# V1_2-.net
KiCad netlist of a schematic drawn in Altium Designer
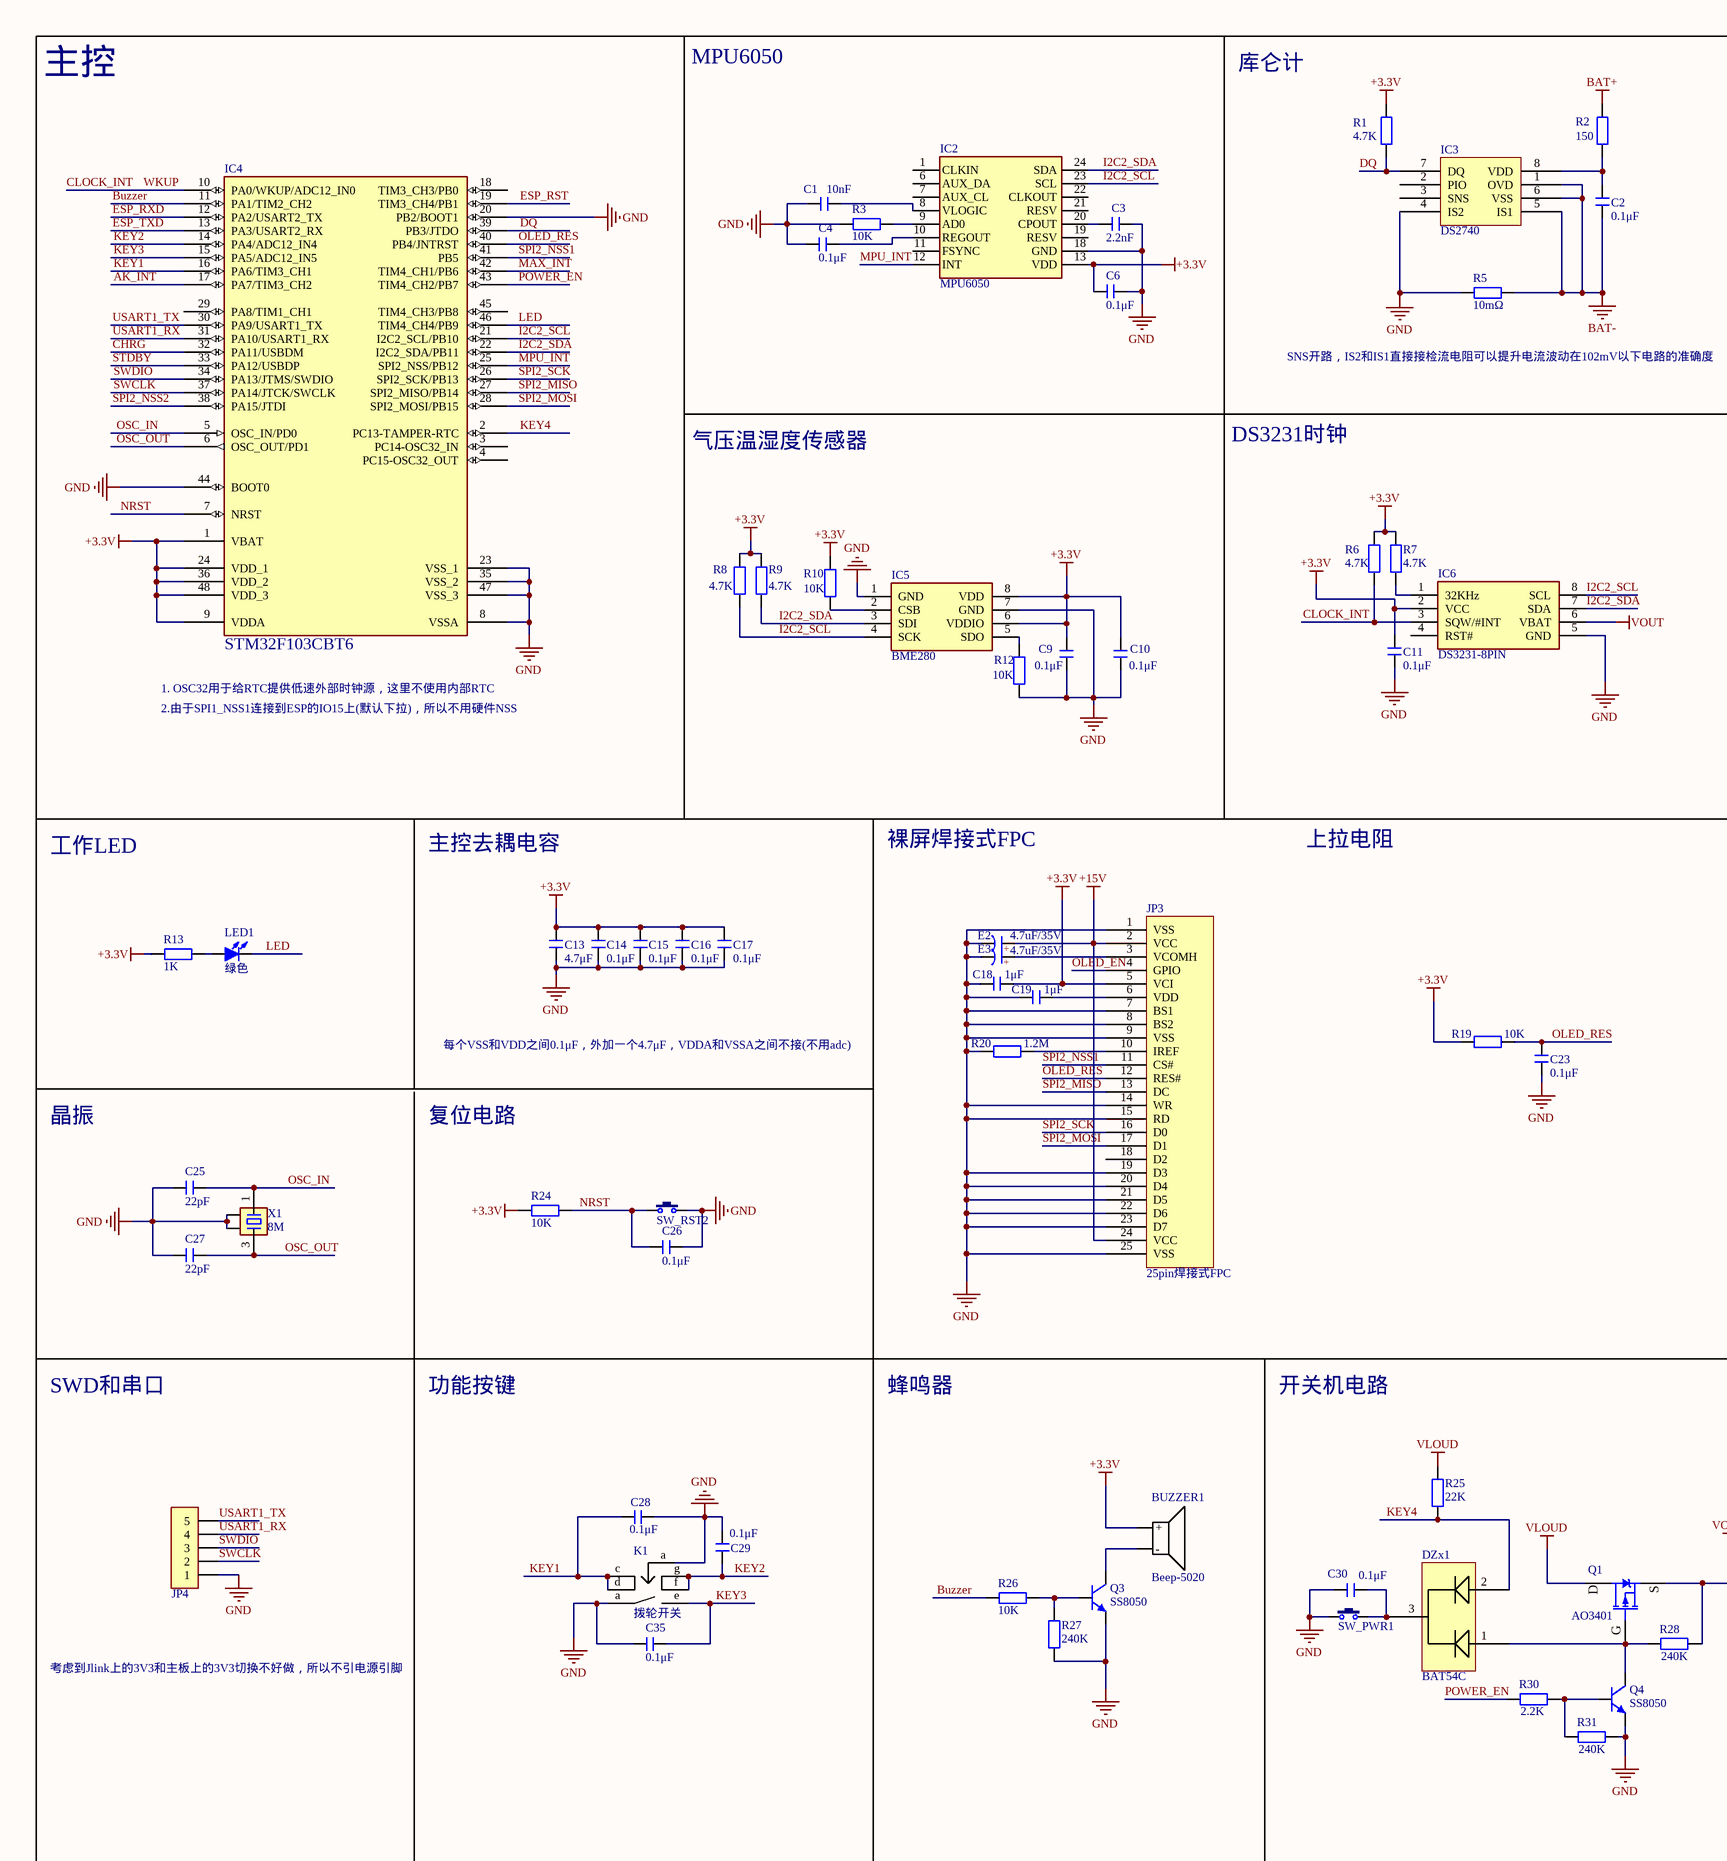
[diagram p0: V1.2-核心板.SchDoc, left]
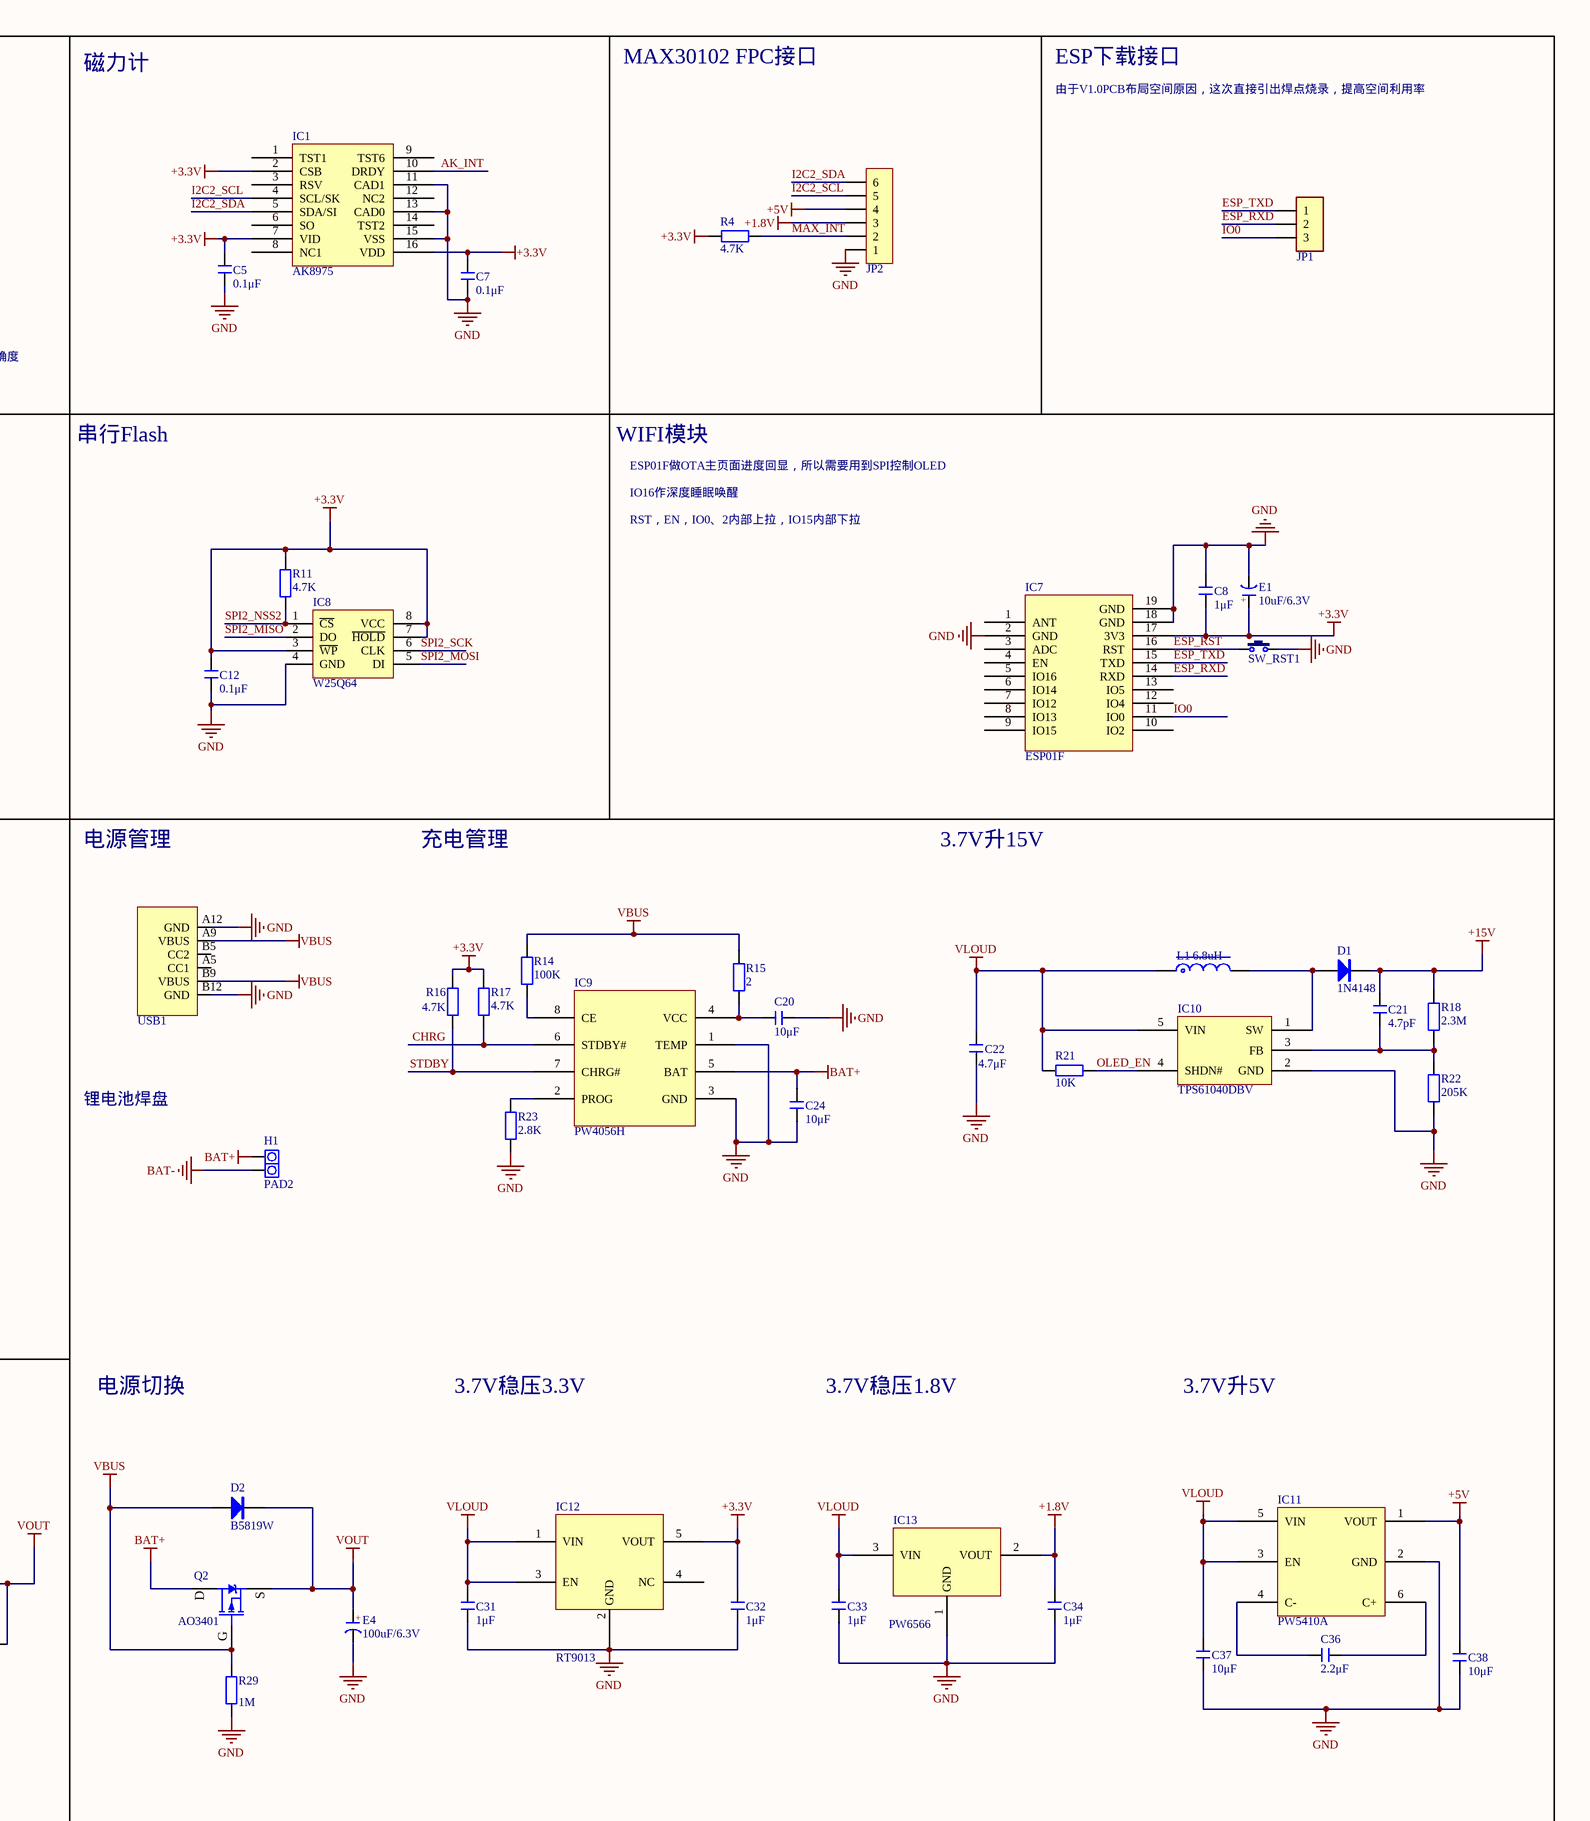
[diagram p1: V1.2-核心板.SchDoc, right]

(export (version "E")
  (design (tool "Eeschema 10.0.6"))
  (components
    (comp (ref "BUZZER1")
      (value "Beep-5020")
      (footprint "5020BUZZER")
      (description "贴片蜂鸣器5020最小封装")
      (libsource (lib "STM32_Watch") (part "Beep-5020"))
    )
    (comp (ref "C1")
      (value "10nF")
      (footprint "C 0603_L")
      (description "无极性贴片电容")
      (fields (field (name "版权归属") "源创客"))
      (libsource (lib "STM32_Watch") (part "C"))
    )
    (comp (ref "C2")
      (value "0.1μF")
      (footprint "C 0603_L")
      (description "无极性贴片电容")
      (fields (field (name "版权归属") "源创客"))
      (libsource (lib "STM32_Watch") (part "C"))
    )
    (comp (ref "C3")
      (value "2.2nF")
      (footprint "C 0603_L")
      (description "无极性贴片电容")
      (fields (field (name "版权归属") "源创客"))
      (libsource (lib "STM32_Watch") (part "C"))
    )
    (comp (ref "C4")
      (value "0.1μF")
      (footprint "C 0603_L")
      (description "无极性贴片电容")
      (fields (field (name "版权归属") "源创客"))
      (libsource (lib "STM32_Watch") (part "C"))
    )
    (comp (ref "C5")
      (value "0.1μF")
      (footprint "C 0603_L")
      (description "无极性贴片电容")
      (fields (field (name "版权归属") "源创客"))
      (libsource (lib "STM32_Watch") (part "C"))
    )
    (comp (ref "C6")
      (value "0.1μF")
      (footprint "C 0603_L")
      (description "无极性贴片电容")
      (fields (field (name "版权归属") "源创客"))
      (libsource (lib "STM32_Watch") (part "C"))
    )
    (comp (ref "C7")
      (value "0.1μF")
      (footprint "C 0603_L")
      (description "无极性贴片电容")
      (fields (field (name "版权归属") "源创客"))
      (libsource (lib "STM32_Watch") (part "C"))
    )
    (comp (ref "C8")
      (value "1μF")
      (footprint "C 0603_L")
      (description "无极性贴片电容")
      (fields (field (name "版权归属") "源创客"))
      (libsource (lib "STM32_Watch") (part "C"))
    )
    (comp (ref "C9")
      (value "0.1μF")
      (footprint "C 0603_L")
      (description "无极性贴片电容")
      (fields (field (name "版权归属") "源创客"))
      (libsource (lib "STM32_Watch") (part "C"))
    )
    (comp (ref "C10")
      (value "0.1μF")
      (footprint "C 0603_L")
      (description "无极性贴片电容")
      (fields (field (name "版权归属") "源创客"))
      (libsource (lib "STM32_Watch") (part "C"))
    )
    (comp (ref "C11")
      (value "0.1μF")
      (footprint "C 0603_L")
      (description "无极性贴片电容")
      (fields (field (name "版权归属") "源创客"))
      (libsource (lib "STM32_Watch") (part "C"))
    )
    (comp (ref "C12")
      (value "0.1μF")
      (footprint "C 0603_L")
      (description "无极性贴片电容")
      (fields (field (name "版权归属") "源创客"))
      (libsource (lib "STM32_Watch") (part "C"))
    )
    (comp (ref "C13")
      (value "4.7μF")
      (footprint "C 0603_L")
      (description "无极性贴片电容")
      (fields (field (name "版权归属") "源创客"))
      (libsource (lib "STM32_Watch") (part "C"))
    )
    (comp (ref "C14")
      (value "0.1μF")
      (footprint "C 0603_L")
      (description "无极性贴片电容")
      (fields (field (name "版权归属") "源创客"))
      (libsource (lib "STM32_Watch") (part "C"))
    )
    (comp (ref "C15")
      (value "0.1μF")
      (footprint "C 0603_L")
      (description "无极性贴片电容")
      (fields (field (name "版权归属") "源创客"))
      (libsource (lib "STM32_Watch") (part "C"))
    )
    (comp (ref "C16")
      (value "0.1μF")
      (footprint "C 0603_L")
      (description "无极性贴片电容")
      (fields (field (name "版权归属") "源创客"))
      (libsource (lib "STM32_Watch") (part "C"))
    )
    (comp (ref "C17")
      (value "0.1μF")
      (footprint "C 0603_L")
      (description "无极性贴片电容")
      (fields (field (name "版权归属") "源创客"))
      (libsource (lib "STM32_Watch") (part "C"))
    )
    (comp (ref "C18")
      (value "1μF")
      (footprint "C 0603_L")
      (description "无极性贴片电容")
      (fields (field (name "版权归属") "源创客"))
      (libsource (lib "STM32_Watch") (part "C"))
    )
    (comp (ref "C19")
      (value "1μF")
      (footprint "C 0603_L")
      (description "无极性贴片电容")
      (fields (field (name "版权归属") "源创客"))
      (libsource (lib "STM32_Watch") (part "C"))
    )
    (comp (ref "C20")
      (value "10μF")
      (footprint "C 0603_L")
      (description "无极性贴片电容")
      (fields (field (name "版权归属") "源创客"))
      (libsource (lib "STM32_Watch") (part "C"))
    )
    (comp (ref "C21")
      (value "4.7pF")
      (footprint "C 0603_L")
      (description "无极性贴片电容")
      (fields (field (name "版权归属") "源创客"))
      (libsource (lib "STM32_Watch") (part "C"))
    )
    (comp (ref "C22")
      (value "4.7μF")
      (footprint "C 0603_L")
      (description "无极性贴片电容")
      (fields (field (name "版权归属") "源创客"))
      (libsource (lib "STM32_Watch") (part "C"))
    )
    (comp (ref "C23")
      (value "0.1μF")
      (footprint "C 0603_L")
      (description "无极性贴片电容")
      (fields (field (name "版权归属") "源创客"))
      (libsource (lib "STM32_Watch") (part "C"))
    )
    (comp (ref "C24")
      (value "10μF")
      (footprint "C 0603_L")
      (description "无极性贴片电容")
      (fields (field (name "版权归属") "源创客"))
      (libsource (lib "STM32_Watch") (part "C"))
    )
    (comp (ref "C25")
      (value "22pF")
      (footprint "C 0603_L")
      (description "无极性贴片电容")
      (fields (field (name "版权归属") "源创客"))
      (libsource (lib "STM32_Watch") (part "C"))
    )
    (comp (ref "C26")
      (value "0.1μF")
      (footprint "C 0603_L")
      (description "无极性贴片电容")
      (fields (field (name "版权归属") "源创客"))
      (libsource (lib "STM32_Watch") (part "C"))
    )
    (comp (ref "C27")
      (value "22pF")
      (footprint "C 0603_L")
      (description "无极性贴片电容")
      (fields (field (name "版权归属") "源创客"))
      (libsource (lib "STM32_Watch") (part "C"))
    )
    (comp (ref "C28")
      (value "0.1μF")
      (footprint "C 0603_L")
      (description "无极性贴片电容")
      (fields (field (name "版权归属") "源创客"))
      (libsource (lib "STM32_Watch") (part "C"))
    )
    (comp (ref "C29")
      (value "0.1μF")
      (footprint "C 0603_L")
      (description "无极性贴片电容")
      (fields (field (name "版权归属") "源创客"))
      (libsource (lib "STM32_Watch") (part "C"))
    )
    (comp (ref "C30")
      (value "0.1μF")
      (footprint "C 0603_L")
      (description "无极性贴片电容")
      (fields (field (name "版权归属") "源创客"))
      (libsource (lib "STM32_Watch") (part "C"))
    )
    (comp (ref "C31")
      (value "1μF")
      (footprint "C 0603_L")
      (description "无极性贴片电容")
      (fields (field (name "版权归属") "源创客"))
      (libsource (lib "STM32_Watch") (part "C"))
    )
    (comp (ref "C32")
      (value "1μF")
      (footprint "C 0603_L")
      (description "无极性贴片电容")
      (fields (field (name "版权归属") "源创客"))
      (libsource (lib "STM32_Watch") (part "C"))
    )
    (comp (ref "C33")
      (value "1μF")
      (footprint "C 0603_L")
      (description "无极性贴片电容")
      (fields (field (name "版权归属") "源创客"))
      (libsource (lib "STM32_Watch") (part "C"))
    )
    (comp (ref "C34")
      (value "1μF")
      (footprint "C 0603_L")
      (description "无极性贴片电容")
      (fields (field (name "版权归属") "源创客"))
      (libsource (lib "STM32_Watch") (part "C"))
    )
    (comp (ref "C35")
      (value "0.1μF")
      (footprint "C 0603_L")
      (description "无极性贴片电容")
      (fields (field (name "版权归属") "源创客"))
      (libsource (lib "STM32_Watch") (part "C"))
    )
    (comp (ref "C36")
      (value "2.2μF")
      (footprint "C 0603_L")
      (description "无极性贴片电容")
      (fields (field (name "版权归属") "源创客"))
      (libsource (lib "STM32_Watch") (part "C"))
    )
    (comp (ref "C37")
      (value "10μF")
      (footprint "C 0603_L")
      (description "无极性贴片电容")
      (fields (field (name "版权归属") "源创客"))
      (libsource (lib "STM32_Watch") (part "C"))
    )
    (comp (ref "C38")
      (value "10μF")
      (footprint "C 0603_L")
      (description "无极性贴片电容")
      (fields (field (name "版权归属") "源创客"))
      (libsource (lib "STM32_Watch") (part "C"))
    )
    (comp (ref "D1")
      (value "1N4148")
      (footprint "SOD-123")
      (description "高速开关二极管")
      (fields (field (name "版权归属") "源创客"))
      (libsource (lib "STM32_Watch") (part "1N4148"))
    )
    (comp (ref "D2")
      (value "B5819W")
      (footprint "SOD-123")
      (description "肖特基二极管")
      (fields (field (name "版权归属") "源创客"))
      (libsource (lib "STM32_Watch") (part "B5819W"))
    )
    (comp (ref "DZx1")
      (value "BAT54C")
      (footprint "SOT23-3N")
      (description "双肖特基，共阴极")
      (libsource (lib "STM32_Watch") (part "BAT54C"))
    )
    (comp (ref "E1")
      (value "10uF/6.3V")
      (footprint "CD A(3216)")
      (description "贴片钽电容")
      (fields (field (name "版权归属") "源创客"))
      (libsource (lib "") (part "C-CD_1"))
    )
    (comp (ref "E2")
      (value "4.7uF/35V")
      (footprint "CD A(3216)")
      (description "贴片钽电容")
      (fields (field (name "版权归属") "源创客"))
      (libsource (lib "3.1   - 电阻-电容-电感") (part "C-CD"))
    )
    (comp (ref "E3")
      (value "4.7uF/35V")
      (footprint "CD A(3216)")
      (description "贴片钽电容")
      (fields (field (name "版权归属") "源创客"))
      (libsource (lib "3.1   - 电阻-电容-电感") (part "C-CD"))
    )
    (comp (ref "E4")
      (value "100uF/6.3V")
      (footprint "CD A(3216)")
      (description "贴片钽电容")
      (fields (field (name "版权归属") "源创客"))
      (libsource (lib "") (part "C-CD_1"))
    )
    (comp (ref "H1")
      (value "PAD2")
      (footprint "CHARGE_PAD")
      (description "引线焊盘")
      (fields (field (name "版权归属") "源创客"))
      (libsource (lib "STM32_Watch") (part "PAD2"))
    )
    (comp (ref "IC1")
      (value "AK8975")
      (footprint "QFN16 4x4_M")
      (description "采用高灵敏度霍尔传感器技术的三轴电子罗盘IC。\r\n最适合步行城市导航，用于手机和其他便携式设备")
      (libsource (lib "STM32_Watch") (part "AK8975"))
    )
    (comp (ref "IC2")
      (value "MPU6050")
      (footprint "QFN24 4x4_M")
      (description "陀螺仪")
      (libsource (lib "STM32_Watch") (part "MPU6050"))
    )
    (comp (ref "IC3")
      (value "DS2740")
      (footprint "MSOP8_L")
      (description "高精度库仑计")
      (libsource (lib "STM32_Watch") (part "DS2740"))
    )
    (comp (ref "IC4")
      (value "STM32F103CBT6")
      (footprint "LQFP48 7X7_M")
      (description "Flash:128/RAM:20/IO:48")
      (fields (field (name "版权归属") "源创客"))
      (libsource (lib "STM32_Watch") (part "STM32F103CB"))
    )
    (comp (ref "IC5")
      (value "BME280")
      (footprint "BME280")
      (description "气压，湿度，温度传感器")
      (libsource (lib "STM32_Watch") (part "BME280"))
    )
    (comp (ref "IC6")
      (value "DS3231-8PIN")
      (footprint "SOP8_N")
      (libsource (lib "STM32_Watch") (part "DS3231-8PIN"))
    )
    (comp (ref "IC7") (value "ESP01F") (footprint "ESP-01F") (libsource (lib "STM32_Watch") (part "ESP01F")))
    (comp (ref "IC8")
      (value "W25Q64")
      (footprint "SOP8W_N")
      (description "外置Flash")
      (fields (field (name "版权归属") "源创客"))
      (libsource (lib "1.1   - IC芯片") (part "W25Qxx"))
    )
    (comp (ref "IC9")
      (value "PW4056H")
      (footprint "SOP-8_L4.9-W3.9-P1.27-LS6.0-BL-EP3.1")
      (description "PW4056H 是一款完整的采用恒定电流/恒定电压的高压、大电流、单节鲤离子电池线性充电IC，最高耐压可达 28V，6.5V 自动过压保护，充电电流可达 1A。")
      (libsource (lib "STM32_Watch") (part "PW4056H"))
    )
    (comp (ref "IC10")
      (value "TPS61040DBV")
      (footprint "SOT23-5L")
      (description "28V、400mA 开关升压转换器，适用于 LCD 和白光 LED")
      (libsource (lib "STM32_Watch") (part "TPS61040DBV"))
    )
    (comp (ref "IC11")
      (value "PW5410A")
      (footprint "SOT23-6")
      (description "低噪声，恒频 1.2MHZ，输入电压范围2.7v-5v，5v固定输出电压，输出电流250mA的DCDC升压")
      (libsource (lib "STM32_Watch") (part "PW5410A"))
    )
    (comp (ref "IC12")
      (value "RT9013")
      (footprint "SOT23-5L")
      (libsource (lib "STM32_Watch") (part "RT9013"))
    )
    (comp (ref "IC13")
      (value "PW6566")
      (footprint "SOT23-3L")
      (description "PW6566 系列是使用 CMOS 技术开发的低压差，高精度 输出电压，低消耗电流正电压型电压稳压器")
      (libsource (lib "STM32_Watch") (part "PW6566"))
    )
    (comp (ref "JP1")
      (value "HDR-1X3")
      (footprint "TEST_POINT_3")
      (description "3P接插件")
      (fields (field (name "版权归属") "源创客"))
      (libsource (lib "STM32_Watch") (part "Header 3"))
    )
    (comp (ref "JP2")
      (value "FPC1.0-6P")
      (footprint "FPC0.5 2H-WS-6P")
      (description "FPC连接器")
      (fields (field (name "版权归属") "源创客"))
      (libsource (lib "STM32_Watch") (part "FPC-6P"))
    )
    (comp (ref "JP3")
      (value "25pin焊接式FPC")
      (footprint "25pin焊接式FPC")
      (libsource (lib "STM32_Watch") (part "25pin焊接式FPC"))
    )
    (comp (ref "JP4")
      (value "HDR-1X5")
      (footprint "TEST_POINT_5")
      (description "5P接插件")
      (fields (field (name "版权归属") "源创客"))
      (libsource (lib "STM32_Watch") (part "Header 5"))
    )
    (comp (ref "K1") (value "拨轮开关") (footprint "拨轮开关") (libsource (lib "STM32_Watch") (part "拨轮开关")))
    (comp (ref "L1")
      (value "6.8uH")
      (footprint "NR3015")
      (description "NR磁胶电感")
      (fields (field (name "版权归属") "源创客"))
      (libsource (lib "STM32_Watch") (part "L-NR"))
    )
    (comp (ref "LED1")
      (value "绿色")
      (footprint "LED 0603G")
      (description "贴片LED")
      (fields (field (name "版权归属") "源创客"))
      (libsource (lib "STM32_Watch") (part "LED-SMD"))
    )
    (comp (ref "Q1")
      (value "AO3401")
      (footprint "SOT23-3N")
      (description "P沟道场效应管")
      (fields (field (name "版权归属") "源创客"))
      (libsource (lib "STM32_Watch") (part "AO3401"))
    )
    (comp (ref "Q2")
      (value "AO3401")
      (footprint "SOT23-3N")
      (description "P沟道场效应管")
      (fields (field (name "版权归属") "源创客"))
      (libsource (lib "STM32_Watch") (part "AO3401"))
    )
    (comp (ref "Q3")
      (value "SS8050")
      (footprint "SOT23-3N")
      (description "高频放大-NPN型")
      (fields (field (name "版权归属") "源创客"))
      (libsource (lib "STM32_Watch") (part "8050-SMD"))
    )
    (comp (ref "Q4")
      (value "SS8050")
      (footprint "SOT23-3N")
      (description "高频放大-NPN型")
      (fields (field (name "版权归属") "源创客"))
      (libsource (lib "STM32_Watch") (part "8050-SMD"))
    )
    (comp (ref "R1")
      (value "4.7K")
      (footprint "R 0603_L")
      (description "贴片电阻")
      (fields (field (name "版权归属") "源创客"))
      (libsource (lib "STM32_Watch") (part "R"))
    )
    (comp (ref "R2")
      (value "150")
      (footprint "R 0603_L")
      (description "贴片电阻")
      (fields (field (name "版权归属") "源创客"))
      (libsource (lib "STM32_Watch") (part "R"))
    )
    (comp (ref "R3")
      (value "10K")
      (footprint "R 0603_L")
      (description "贴片电阻")
      (fields (field (name "版权归属") "源创客"))
      (libsource (lib "STM32_Watch") (part "R"))
    )
    (comp (ref "R4")
      (value "4.7K")
      (footprint "R 0603_L")
      (description "贴片电阻")
      (fields (field (name "版权归属") "源创客"))
      (libsource (lib "STM32_Watch") (part "R"))
    )
    (comp (ref "R5")
      (value "10mΩ")
      (footprint "R 0603_L")
      (description "贴片电阻")
      (fields (field (name "版权归属") "源创客"))
      (libsource (lib "STM32_Watch") (part "R"))
    )
    (comp (ref "R6")
      (value "4.7K")
      (footprint "R 0603_L")
      (description "贴片电阻")
      (fields (field (name "版权归属") "源创客"))
      (libsource (lib "STM32_Watch") (part "R"))
    )
    (comp (ref "R7")
      (value "4.7K")
      (footprint "R 0603_L")
      (description "贴片电阻")
      (fields (field (name "版权归属") "源创客"))
      (libsource (lib "STM32_Watch") (part "R"))
    )
    (comp (ref "R8")
      (value "4.7K")
      (footprint "R 0603_L")
      (description "贴片电阻")
      (fields (field (name "版权归属") "源创客"))
      (libsource (lib "STM32_Watch") (part "R"))
    )
    (comp (ref "R9")
      (value "4.7K")
      (footprint "R 0603_L")
      (description "贴片电阻")
      (fields (field (name "版权归属") "源创客"))
      (libsource (lib "STM32_Watch") (part "R"))
    )
    (comp (ref "R10")
      (value "10K")
      (footprint "R 0603_L")
      (description "贴片电阻")
      (fields (field (name "版权归属") "源创客"))
      (libsource (lib "STM32_Watch") (part "R"))
    )
    (comp (ref "R11")
      (value "4.7K")
      (footprint "R 0603_L")
      (description "贴片电阻")
      (fields (field (name "版权归属") "源创客"))
      (libsource (lib "STM32_Watch") (part "R"))
    )
    (comp (ref "R12")
      (value "10K")
      (footprint "R 0603_L")
      (description "贴片电阻")
      (fields (field (name "版权归属") "源创客"))
      (libsource (lib "STM32_Watch") (part "R"))
    )
    (comp (ref "R13")
      (value "1K")
      (footprint "R 0603_L")
      (description "贴片电阻")
      (fields (field (name "版权归属") "源创客"))
      (libsource (lib "STM32_Watch") (part "R"))
    )
    (comp (ref "R14")
      (value "100K")
      (footprint "R 0603_L")
      (description "贴片电阻")
      (fields (field (name "版权归属") "源创客"))
      (libsource (lib "STM32_Watch") (part "R"))
    )
    (comp (ref "R15")
      (value "2")
      (footprint "R 0603_L")
      (description "贴片电阻")
      (fields (field (name "版权归属") "源创客"))
      (libsource (lib "STM32_Watch") (part "R"))
    )
    (comp (ref "R16")
      (value "4.7K")
      (footprint "R 0603_L")
      (description "贴片电阻")
      (fields (field (name "版权归属") "源创客"))
      (libsource (lib "STM32_Watch") (part "R"))
    )
    (comp (ref "R17")
      (value "4.7K")
      (footprint "R 0603_L")
      (description "贴片电阻")
      (fields (field (name "版权归属") "源创客"))
      (libsource (lib "STM32_Watch") (part "R"))
    )
    (comp (ref "R18")
      (value "2.3M")
      (footprint "R 0603_L")
      (description "贴片电阻")
      (fields (field (name "版权归属") "源创客"))
      (libsource (lib "STM32_Watch") (part "R"))
    )
    (comp (ref "R19")
      (value "10K")
      (footprint "R 0603_L")
      (description "贴片电阻")
      (fields (field (name "版权归属") "源创客"))
      (libsource (lib "STM32_Watch") (part "R"))
    )
    (comp (ref "R20")
      (value "1.2M")
      (footprint "R 0603_L")
      (description "贴片电阻")
      (fields (field (name "版权归属") "源创客"))
      (libsource (lib "STM32_Watch") (part "R"))
    )
    (comp (ref "R21")
      (value "10K")
      (footprint "R 0603_L")
      (description "贴片电阻")
      (fields (field (name "版权归属") "源创客"))
      (libsource (lib "STM32_Watch") (part "R"))
    )
    (comp (ref "R22")
      (value "205K")
      (footprint "R 0603_L")
      (description "贴片电阻")
      (fields (field (name "版权归属") "源创客"))
      (libsource (lib "STM32_Watch") (part "R"))
    )
    (comp (ref "R23")
      (value "2.8K")
      (footprint "R 0603_L")
      (description "贴片电阻")
      (fields (field (name "版权归属") "源创客"))
      (libsource (lib "STM32_Watch") (part "R"))
    )
    (comp (ref "R24")
      (value "10K")
      (footprint "R 0603_L")
      (description "贴片电阻")
      (fields (field (name "版权归属") "源创客"))
      (libsource (lib "STM32_Watch") (part "R"))
    )
    (comp (ref "R25")
      (value "22K")
      (footprint "R 0603_L")
      (description "贴片电阻")
      (fields (field (name "版权归属") "源创客"))
      (libsource (lib "STM32_Watch") (part "R"))
    )
    (comp (ref "R26")
      (value "10K")
      (footprint "R 0603_L")
      (description "贴片电阻")
      (fields (field (name "版权归属") "源创客"))
      (libsource (lib "STM32_Watch") (part "R"))
    )
    (comp (ref "R27")
      (value "240K")
      (footprint "R 0603_L")
      (description "贴片电阻")
      (fields (field (name "版权归属") "源创客"))
      (libsource (lib "STM32_Watch") (part "R"))
    )
    (comp (ref "R28")
      (value "240K")
      (footprint "R 0603_L")
      (description "贴片电阻")
      (fields (field (name "版权归属") "源创客"))
      (libsource (lib "STM32_Watch") (part "R"))
    )
    (comp (ref "R29")
      (value "1M")
      (footprint "R 0603_L")
      (description "贴片电阻")
      (fields (field (name "版权归属") "源创客"))
      (libsource (lib "STM32_Watch") (part "R"))
    )
    (comp (ref "R30")
      (value "2.2K")
      (footprint "R 0603_L")
      (description "贴片电阻")
      (fields (field (name "版权归属") "源创客"))
      (libsource (lib "STM32_Watch") (part "R"))
    )
    (comp (ref "R31")
      (value "240K")
      (footprint "R 0603_L")
      (description "贴片电阻")
      (fields (field (name "版权归属") "源创客"))
      (libsource (lib "STM32_Watch") (part "R"))
    )
    (comp (ref "SW_PWR1")
      (value "3")
      (footprint "KEY-SMD_UK-B0264-SP25Y")
      (description "2x4x3.5轻触开关")
      (fields (field (name "版权归属") "源创客"))
      (libsource (lib "STM32_Watch") (part "TSW 2x4x3.5"))
    )
    (comp (ref "SW_RST1")
      (value "3x4x2")
      (footprint "SW-SMD_L4.0-W3.0-LS4.6")
      (description "3x4x2开关")
      (fields (field (name "版权归属") "源创客"))
      (libsource (lib "STM32_Watch") (part "TSW 3x4x2"))
    )
    (comp (ref "SW_RST2")
      (value "3x4x2")
      (footprint "SW-SMD_L4.0-W3.0-LS4.6")
      (description "3x4x2开关")
      (fields (field (name "版权归属") "源创客"))
      (libsource (lib "STM32_Watch") (part "TSW 3x4x2"))
    )
    (comp (ref "USB1")
      (value "918-418K2023S40006")
      (footprint "USB-C-SMD_918-418K2023S40006")
      (description "连接器类型:Type-C;标准:USB 3.1;公母:母座;触点数量:6;端口数量:1;安装方式:卧贴;额定电流 - 电源:-;工作温度范围:-40℃~+85℃;")
      (fields (field (name "MANUFACTURER") "精拓金"))
      (libsource (lib "STM32_Watch") (part "TYPE-C 6PIN"))
    )
    (comp (ref "X1")
      (value "8M")
      (footprint "OSC 3225-4P")
      (description "4脚无源晶振")
      (fields (field (name "版权归属") "源创客"))
      (libsource (lib "STM32_Watch") (part "XTAL-4P"))
    )
  )
  (nets
    (net (code "1") (name "+1.8V") (class "Default")
      (node (ref "C34") (pin "1") (pinfunction "1_1") (pintype "passive"))
      (node (ref "IC13") (pin "2") (pinfunction "VOUT_2") (pintype "passive"))
      (node (ref "JP2") (pin "3") (pinfunction "3_3") (pintype "passive"))
    )
    (net (code "2") (name "+3.3V") (class "Default")
      (node (ref "BUZZER1") (pin "1") (pinfunction "+_1") (pintype "passive"))
      (node (ref "C10") (pin "1") (pinfunction "1_1") (pintype "passive"))
      (node (ref "C11") (pin "1") (pinfunction "1_1") (pintype "passive"))
      (node (ref "C12") (pin "2") (pinfunction "2_2") (pintype "passive"))
      (node (ref "C13") (pin "2") (pinfunction "2_2") (pintype "passive"))
      (node (ref "C14") (pin "2") (pinfunction "2_2") (pintype "passive"))
      (node (ref "C15") (pin "2") (pinfunction "2_2") (pintype "passive"))
      (node (ref "C16") (pin "2") (pinfunction "2_2") (pintype "passive"))
      (node (ref "C17") (pin "2") (pinfunction "2_2") (pintype "passive"))
      (node (ref "C18") (pin "2") (pinfunction "2_2") (pintype "passive"))
      (node (ref "C32") (pin "1") (pinfunction "1_1") (pintype "passive"))
      (node (ref "C5") (pin "2") (pinfunction "2_2") (pintype "passive"))
      (node (ref "C6") (pin "2") (pinfunction "2_2") (pintype "passive"))
      (node (ref "C7") (pin "2") (pinfunction "2_2") (pintype "passive"))
      (node (ref "C8") (pin "1") (pinfunction "1_1") (pintype "passive"))
      (node (ref "C9") (pin "1") (pinfunction "1_1") (pintype "passive"))
      (node (ref "E1") (pin "1") (pinfunction "A_1") (pintype "passive"))
      (node (ref "IC1") (pin "16") (pinfunction "VDD_16") (pintype "passive"))
      (node (ref "IC1") (pin "2") (pinfunction "CSB_2") (pintype "passive"))
      (node (ref "IC1") (pin "7") (pinfunction "VID_7") (pintype "passive"))
      (node (ref "IC12") (pin "5") (pinfunction "VOUT_5") (pintype "passive"))
      (node (ref "IC2") (pin "13") (pinfunction "VDD_13") (pintype "passive"))
      (node (ref "IC4") (pin "1") (pinfunction "VBAT_1") (pintype "power_in"))
      (node (ref "IC4") (pin "24") (pinfunction "VDD_1_24") (pintype "power_in"))
      (node (ref "IC4") (pin "36") (pinfunction "VDD_2_36") (pintype "power_in"))
      (node (ref "IC4") (pin "48") (pinfunction "VDD_3_48") (pintype "power_in"))
      (node (ref "IC4") (pin "9") (pinfunction "VDDA_9") (pintype "power_in"))
      (node (ref "IC5") (pin "6") (pinfunction "VDDIO_6") (pintype "passive"))
      (node (ref "IC5") (pin "8") (pinfunction "VDD_8") (pintype "passive"))
      (node (ref "IC6") (pin "2") (pinfunction "VCC_2") (pintype "passive"))
      (node (ref "IC7") (pin "17") (pinfunction "3V3_17") (pintype "passive"))
      (node (ref "IC8") (pin "3") (pinfunction "~{WP}_3") (pintype "passive"))
      (node (ref "IC8") (pin "7") (pinfunction "~{HOLD}_7") (pintype "passive"))
      (node (ref "IC8") (pin "8") (pinfunction "VCC_8") (pintype "passive"))
      (node (ref "JP3") (pin "5") (pinfunction "VCI_5") (pintype "passive"))
      (node (ref "R1") (pin "2") (pinfunction "2_2") (pintype "passive"))
      (node (ref "R10") (pin "2") (pinfunction "2_2") (pintype "passive"))
      (node (ref "R11") (pin "2") (pinfunction "2_2") (pintype "passive"))
      (node (ref "R13") (pin "2") (pinfunction "2_2") (pintype "passive"))
      (node (ref "R16") (pin "2") (pinfunction "2_2") (pintype "passive"))
      (node (ref "R17") (pin "2") (pinfunction "2_2") (pintype "passive"))
      (node (ref "R19") (pin "1") (pinfunction "1_1") (pintype "passive"))
      (node (ref "R24") (pin "2") (pinfunction "2_2") (pintype "passive"))
      (node (ref "R4") (pin "2") (pinfunction "2_2") (pintype "passive"))
      (node (ref "R6") (pin "1") (pinfunction "1_1") (pintype "passive"))
      (node (ref "R7") (pin "1") (pinfunction "1_1") (pintype "passive"))
      (node (ref "R8") (pin "1") (pinfunction "1_1") (pintype "passive"))
      (node (ref "R9") (pin "1") (pinfunction "1_1") (pintype "passive"))
    )
    (net (code "3") (name "+5V") (class "Default")
      (node (ref "C38") (pin "1") (pinfunction "1_1") (pintype "passive"))
      (node (ref "IC11") (pin "1") (pinfunction "VOUT_1") (pintype "passive"))
      (node (ref "JP2") (pin "4") (pinfunction "4_4") (pintype "passive"))
    )
    (net (code "4") (name "+15V") (class "Default")
      (node (ref "C21") (pin "2") (pinfunction "2_2") (pintype "passive"))
      (node (ref "D1") (pin "2") (pinfunction "K_2") (pintype "passive"))
      (node (ref "E2") (pin "1") (pinfunction "A_1") (pintype "passive"))
      (node (ref "JP3") (pin "2") (pinfunction "VCC_2") (pintype "passive"))
      (node (ref "JP3") (pin "24") (pinfunction "VCC_24") (pintype "passive"))
      (node (ref "R18") (pin "2") (pinfunction "2_2") (pintype "passive"))
    )
    (net (code "5") (name "/AK_INT") (class "Default")
      (node (ref "IC1") (pin "10") (pinfunction "DRDY_10") (pintype "passive"))
      (node (ref "IC4") (pin "17") (pinfunction "PA7/TIM3_CH2_17") (pintype "bidirectional"))
    )
    (net (code "6") (name "/Buzzer") (class "Default")
      (node (ref "IC4") (pin "11") (pinfunction "PA1/TIM2_CH2_11") (pintype "bidirectional"))
      (node (ref "R26") (pin "1") (pinfunction "1_1") (pintype "passive"))
    )
    (net (code "7") (name "/CHRG") (class "Default")
      (node (ref "IC4") (pin "32") (pinfunction "PA11/USBDM_32") (pintype "bidirectional"))
      (node (ref "IC9") (pin "6") (pinfunction "STDBY#_6") (pintype "passive"))
      (node (ref "R17") (pin "1") (pinfunction "1_1") (pintype "passive"))
    )
    (net (code "8") (name "/CLOCK_INT") (class "Default")
      (node (ref "IC4") (pin "10") (pinfunction "PA0/WKUP/ADC12_IN0_10") (pintype "bidirectional"))
      (node (ref "IC6") (pin "3") (pinfunction "SQW/#INT_3") (pintype "passive"))
      (node (ref "R6") (pin "2") (pinfunction "2_2") (pintype "passive"))
    )
    (net (code "9") (name "/DQ") (class "Default")
      (node (ref "IC3") (pin "7") (pinfunction "DQ_7") (pintype "passive"))
      (node (ref "IC4") (pin "39") (pinfunction "PB3/JTDO_39") (pintype "bidirectional"))
      (node (ref "R1") (pin "1") (pinfunction "1_1") (pintype "passive"))
    )
    (net (code "10") (name "/ESP_RST") (class "Default")
      (node (ref "IC4") (pin "19") (pinfunction "TIM3_CH4/PB1_19") (pintype "bidirectional"))
      (node (ref "IC7") (pin "16") (pinfunction "RST_16") (pintype "passive"))
      (node (ref "SW_RST1") (pin "1") (pinfunction "1_1") (pintype "passive"))
    )
    (net (code "11") (name "/ESP_RXD") (class "Default")
      (node (ref "IC4") (pin "12") (pinfunction "PA2/USART2_TX_12") (pintype "bidirectional"))
      (node (ref "IC7") (pin "14") (pinfunction "RXD_14") (pintype "passive"))
      (node (ref "JP1") (pin "2") (pinfunction "2_2") (pintype "passive"))
    )
    (net (code "12") (name "/ESP_TXD") (class "Default")
      (node (ref "IC4") (pin "13") (pinfunction "PA3/USART2_RX_13") (pintype "bidirectional"))
      (node (ref "IC7") (pin "15") (pinfunction "TXD_15") (pintype "passive"))
      (node (ref "JP1") (pin "1") (pinfunction "1_1") (pintype "passive"))
    )
    (net (code "13") (name "/I2C2_SCL") (class "Default")
      (node (ref "IC1") (pin "4") (pinfunction "SCL/SK_4") (pintype "passive"))
      (node (ref "IC2") (pin "23") (pinfunction "SCL_23") (pintype "passive"))
      (node (ref "IC4") (pin "21") (pinfunction "I2C2_SCL/PB10_21") (pintype "bidirectional"))
      (node (ref "IC5") (pin "4") (pinfunction "SCK_4") (pintype "passive"))
      (node (ref "IC6") (pin "8") (pinfunction "SCL_8") (pintype "passive"))
      (node (ref "JP2") (pin "5") (pinfunction "5_5") (pintype "passive"))
      (node (ref "R8") (pin "2") (pinfunction "2_2") (pintype "passive"))
    )
    (net (code "14") (name "/I2C2_SDA") (class "Default")
      (node (ref "IC1") (pin "5") (pinfunction "SDA/SI_5") (pintype "passive"))
      (node (ref "IC2") (pin "24") (pinfunction "SDA_24") (pintype "passive"))
      (node (ref "IC4") (pin "22") (pinfunction "I2C2_SDA/PB11_22") (pintype "bidirectional"))
      (node (ref "IC5") (pin "3") (pinfunction "SDI_3") (pintype "passive"))
      (node (ref "IC6") (pin "7") (pinfunction "SDA_7") (pintype "passive"))
      (node (ref "JP2") (pin "6") (pinfunction "6_6") (pintype "passive"))
      (node (ref "R9") (pin "2") (pinfunction "2_2") (pintype "passive"))
    )
    (net (code "15") (name "/IO0") (class "Default")
      (node (ref "IC7") (pin "11") (pinfunction "IO0_11") (pintype "passive"))
      (node (ref "JP1") (pin "3") (pinfunction "3_3") (pintype "passive"))
    )
    (net (code "16") (name "/KEY1") (class "Default")
      (node (ref "C28") (pin "1") (pinfunction "1_1") (pintype "passive"))
      (node (ref "IC4") (pin "16") (pinfunction "PA6/TIM3_CH1_16") (pintype "bidirectional"))
      (node (ref "K1") (pin "c") (pinfunction "c_c") (pintype "passive"))
      (node (ref "K1") (pin "d") (pinfunction "d_d") (pintype "passive"))
    )
    (net (code "17") (name "/KEY2") (class "Default")
      (node (ref "C29") (pin "1") (pinfunction "1_1") (pintype "passive"))
      (node (ref "IC4") (pin "14") (pinfunction "PA4/ADC12_IN4_14") (pintype "bidirectional"))
      (node (ref "K1") (pin "f") (pinfunction "f_f") (pintype "passive"))
      (node (ref "K1") (pin "g") (pinfunction "g_g") (pintype "passive"))
    )
    (net (code "18") (name "/KEY3") (class "Default")
      (node (ref "C35") (pin "1") (pinfunction "1_1") (pintype "passive"))
      (node (ref "IC4") (pin "15") (pinfunction "PA5/ADC12_IN5_15") (pintype "bidirectional"))
      (node (ref "K1") (pin "e") (pinfunction "e_e") (pintype "passive"))
    )
    (net (code "19") (name "/KEY4") (class "Default")
      (node (ref "DZx1") (pin "2") (pinfunction "2_2") (pintype "passive"))
      (node (ref "IC4") (pin "2") (pinfunction "PC13-TAMPER-RTC_2") (pintype "bidirectional"))
      (node (ref "R25") (pin "2") (pinfunction "2_2") (pintype "passive"))
    )
    (net (code "20") (name "/LED") (class "Default")
      (node (ref "IC4") (pin "46") (pinfunction "TIM4_CH4/PB9_46") (pintype "bidirectional"))
      (node (ref "LED1") (pin "2") (pinfunction "K_2") (pintype "passive"))
    )
    (net (code "21") (name "/MAX_INT") (class "Default")
      (node (ref "IC4") (pin "42") (pinfunction "TIM4_CH1/PB6_42") (pintype "bidirectional"))
      (node (ref "JP2") (pin "2") (pinfunction "2_2") (pintype "passive"))
      (node (ref "R4") (pin "1") (pinfunction "1_1") (pintype "passive"))
    )
    (net (code "22") (name "/MPU_INT") (class "Default")
      (node (ref "IC2") (pin "12") (pinfunction "INT_12") (pintype "passive"))
      (node (ref "IC4") (pin "25") (pinfunction "SPI2_NSS/PB12_25") (pintype "bidirectional"))
    )
    (net (code "23") (name "/NRST") (class "Default")
      (node (ref "C26") (pin "2") (pinfunction "2_2") (pintype "passive"))
      (node (ref "IC4") (pin "7") (pinfunction "NRST_7") (pintype "bidirectional"))
      (node (ref "R24") (pin "1") (pinfunction "1_1") (pintype "passive"))
      (node (ref "SW_RST2") (pin "1") (pinfunction "1_1") (pintype "passive"))
    )
    (net (code "24") (name "/OLED_EN") (class "Default")
      (node (ref "IC10") (pin "4") (pinfunction "SHDN#_4") (pintype "passive"))
      (node (ref "JP3") (pin "4") (pinfunction "GPIO_4") (pintype "passive"))
      (node (ref "R21") (pin "1") (pinfunction "1_1") (pintype "passive"))
    )
    (net (code "25") (name "/OLED_RES") (class "Default")
      (node (ref "C23") (pin "2") (pinfunction "2_2") (pintype "passive"))
      (node (ref "IC4") (pin "40") (pinfunction "PB4/JNTRST_40") (pintype "bidirectional"))
      (node (ref "JP3") (pin "12") (pinfunction "RES#_12") (pintype "passive"))
      (node (ref "R19") (pin "2") (pinfunction "2_2") (pintype "passive"))
    )
    (net (code "26") (name "/OSC_IN") (class "Default")
      (node (ref "C25") (pin "1") (pinfunction "1_1") (pintype "passive"))
      (node (ref "IC4") (pin "5") (pinfunction "OSC_IN/PD0_5") (pintype "input"))
      (node (ref "X1") (pin "1") (pinfunction "1_1") (pintype "passive"))
    )
    (net (code "27") (name "/OSC_OUT") (class "Default")
      (node (ref "C27") (pin "1") (pinfunction "1_1") (pintype "passive"))
      (node (ref "IC4") (pin "6") (pinfunction "OSC_OUT/PD1_6") (pintype "output"))
      (node (ref "X1") (pin "3") (pinfunction "3_3") (pintype "passive"))
    )
    (net (code "28") (name "/POWER_EN") (class "Default")
      (node (ref "IC4") (pin "43") (pinfunction "TIM4_CH2/PB7_43") (pintype "bidirectional"))
      (node (ref "R30") (pin "2") (pinfunction "2_2") (pintype "passive"))
    )
    (net (code "29") (name "/SPI2_MISO") (class "Default")
      (node (ref "IC4") (pin "27") (pinfunction "SPI2_MISO/PB14_27") (pintype "bidirectional"))
      (node (ref "IC8") (pin "2") (pinfunction "DO_2") (pintype "passive"))
      (node (ref "JP3") (pin "13") (pinfunction "DC_13") (pintype "passive"))
    )
    (net (code "30") (name "/SPI2_MOSI") (class "Default")
      (node (ref "IC4") (pin "28") (pinfunction "SPI2_MOSI/PB15_28") (pintype "bidirectional"))
      (node (ref "IC8") (pin "5") (pinfunction "DI_5") (pintype "passive"))
      (node (ref "JP3") (pin "17") (pinfunction "D1_17") (pintype "passive"))
    )
    (net (code "31") (name "/SPI2_NSS1") (class "Default")
      (node (ref "IC4") (pin "41") (pinfunction "PB5_41") (pintype "bidirectional"))
      (node (ref "JP3") (pin "11") (pinfunction "CS#_11") (pintype "passive"))
    )
    (net (code "32") (name "/SPI2_NSS2") (class "Default")
      (node (ref "IC4") (pin "38") (pinfunction "PA15/JTDI_38") (pintype "bidirectional"))
      (node (ref "IC8") (pin "1") (pinfunction "~{CS}_1") (pintype "passive"))
      (node (ref "R11") (pin "1") (pinfunction "1_1") (pintype "passive"))
    )
    (net (code "33") (name "/SPI2_SCK") (class "Default")
      (node (ref "IC4") (pin "26") (pinfunction "SPI2_SCK/PB13_26") (pintype "bidirectional"))
      (node (ref "IC8") (pin "6") (pinfunction "CLK_6") (pintype "passive"))
      (node (ref "JP3") (pin "16") (pinfunction "D0_16") (pintype "passive"))
    )
    (net (code "34") (name "/STDBY") (class "Default")
      (node (ref "IC4") (pin "33") (pinfunction "PA12/USBDP_33") (pintype "bidirectional"))
      (node (ref "IC9") (pin "7") (pinfunction "CHRG#_7") (pintype "passive"))
      (node (ref "R16") (pin "1") (pinfunction "1_1") (pintype "passive"))
    )
    (net (code "35") (name "/SWCLK") (class "Default")
      (node (ref "IC4") (pin "37") (pinfunction "PA14/JTCK/SWCLK_37") (pintype "bidirectional"))
      (node (ref "JP4") (pin "2") (pinfunction "2_2") (pintype "passive"))
    )
    (net (code "36") (name "/SWDIO") (class "Default")
      (node (ref "IC4") (pin "34") (pinfunction "PA13/JTMS/SWDIO_34") (pintype "bidirectional"))
      (node (ref "JP4") (pin "3") (pinfunction "3_3") (pintype "passive"))
    )
    (net (code "37") (name "/USART1_RX") (class "Default")
      (node (ref "IC4") (pin "31") (pinfunction "PA10/USART1_RX_31") (pintype "bidirectional"))
      (node (ref "JP4") (pin "4") (pinfunction "4_4") (pintype "passive"))
    )
    (net (code "38") (name "/USART1_TX") (class "Default")
      (node (ref "IC4") (pin "30") (pinfunction "PA9/USART1_TX_30") (pintype "bidirectional"))
      (node (ref "JP4") (pin "5") (pinfunction "5_5") (pintype "passive"))
    )
    (net (code "39") (name "BAT+") (class "Default")
      (node (ref "C24") (pin "1") (pinfunction "1_1") (pintype "passive"))
      (node (ref "H1") (pin "+") (pinfunction "+_+") (pintype "passive"))
      (node (ref "IC9") (pin "5") (pinfunction "BAT_5") (pintype "passive"))
      (node (ref "Q2") (pin "3") (pinfunction "D_3") (pintype "passive"))
      (node (ref "R2") (pin "2") (pinfunction "2_2") (pintype "passive"))
    )
    (net (code "40") (name "BAT-") (class "Default")
      (node (ref "C2") (pin "1") (pinfunction "1_1") (pintype "passive"))
      (node (ref "H1") (pin "-") (pinfunction "-_-") (pintype "passive"))
      (node (ref "IC3") (pin "1") (pinfunction "OVD_1") (pintype "passive"))
      (node (ref "IC3") (pin "5") (pinfunction "IS1_5") (pintype "passive"))
      (node (ref "IC3") (pin "6") (pinfunction "VSS_6") (pintype "passive"))
      (node (ref "R5") (pin "1") (pinfunction "1_1") (pintype "passive"))
    )
    (net (code "41") (name "GND") (class "Default")
      (node (ref "C1") (pin "2") (pinfunction "2_2") (pintype "passive"))
      (node (ref "C10") (pin "2") (pinfunction "2_2") (pintype "passive"))
      (node (ref "C11") (pin "2") (pinfunction "2_2") (pintype "passive"))
      (node (ref "C12") (pin "1") (pinfunction "1_1") (pintype "passive"))
      (node (ref "C13") (pin "1") (pinfunction "1_1") (pintype "passive"))
      (node (ref "C14") (pin "1") (pinfunction "1_1") (pintype "passive"))
      (node (ref "C15") (pin "1") (pinfunction "1_1") (pintype "passive"))
      (node (ref "C16") (pin "1") (pinfunction "1_1") (pintype "passive"))
      (node (ref "C17") (pin "1") (pinfunction "1_1") (pintype "passive"))
      (node (ref "C18") (pin "1") (pinfunction "1_1") (pintype "passive"))
      (node (ref "C19") (pin "1") (pinfunction "1_1") (pintype "passive"))
      (node (ref "C20") (pin "1") (pinfunction "1_1") (pintype "passive"))
      (node (ref "C22") (pin "1") (pinfunction "1_1") (pintype "passive"))
      (node (ref "C23") (pin "1") (pinfunction "1_1") (pintype "passive"))
      (node (ref "C24") (pin "2") (pinfunction "2_2") (pintype "passive"))
      (node (ref "C25") (pin "2") (pinfunction "2_2") (pintype "passive"))
      (node (ref "C26") (pin "1") (pinfunction "1_1") (pintype "passive"))
      (node (ref "C27") (pin "2") (pinfunction "2_2") (pintype "passive"))
      (node (ref "C28") (pin "2") (pinfunction "2_2") (pintype "passive"))
      (node (ref "C29") (pin "2") (pinfunction "2_2") (pintype "passive"))
      (node (ref "C3") (pin "1") (pinfunction "1_1") (pintype "passive"))
      (node (ref "C30") (pin "1") (pinfunction "1_1") (pintype "passive"))
      (node (ref "C31") (pin "2") (pinfunction "2_2") (pintype "passive"))
      (node (ref "C32") (pin "2") (pinfunction "2_2") (pintype "passive"))
      (node (ref "C33") (pin "2") (pinfunction "2_2") (pintype "passive"))
      (node (ref "C34") (pin "2") (pinfunction "2_2") (pintype "passive"))
      (node (ref "C35") (pin "2") (pinfunction "2_2") (pintype "passive"))
      (node (ref "C37") (pin "1") (pinfunction "1_1") (pintype "passive"))
      (node (ref "C38") (pin "2") (pinfunction "2_2") (pintype "passive"))
      (node (ref "C4") (pin "2") (pinfunction "2_2") (pintype "passive"))
      (node (ref "C5") (pin "1") (pinfunction "1_1") (pintype "passive"))
      (node (ref "C6") (pin "1") (pinfunction "1_1") (pintype "passive"))
      (node (ref "C7") (pin "1") (pinfunction "1_1") (pintype "passive"))
      (node (ref "C8") (pin "2") (pinfunction "2_2") (pintype "passive"))
      (node (ref "C9") (pin "2") (pinfunction "2_2") (pintype "passive"))
      (node (ref "E1") (pin "2") (pinfunction "K_2") (pintype "passive"))
      (node (ref "E2") (pin "2") (pinfunction "K_2") (pintype "passive"))
      (node (ref "E3") (pin "2") (pinfunction "K_2") (pintype "passive"))
      (node (ref "E4") (pin "2") (pinfunction "K_2") (pintype "passive"))
      (node (ref "IC1") (pin "11") (pinfunction "CAD1_11") (pintype "passive"))
      (node (ref "IC1") (pin "13") (pinfunction "CAD0_13") (pintype "passive"))
      (node (ref "IC1") (pin "15") (pinfunction "VSS_15") (pintype "passive"))
      (node (ref "IC10") (pin "2") (pinfunction "GND_2") (pintype "passive"))
      (node (ref "IC11") (pin "2") (pinfunction "GND_2") (pintype "passive"))
      (node (ref "IC12") (pin "2") (pinfunction "GND_2") (pintype "passive"))
      (node (ref "IC13") (pin "1") (pinfunction "GND_1") (pintype "passive"))
      (node (ref "IC2") (pin "18") (pinfunction "GND_18") (pintype "passive"))
      (node (ref "IC3") (pin "4") (pinfunction "IS2_4") (pintype "passive"))
      (node (ref "IC4") (pin "20") (pinfunction "PB2/BOOT1_20") (pintype "bidirectional"))
      (node (ref "IC4") (pin "23") (pinfunction "VSS_1_23") (pintype "power_in"))
      (node (ref "IC4") (pin "35") (pinfunction "VSS_2_35") (pintype "power_in"))
      (node (ref "IC4") (pin "44") (pinfunction "BOOT0_44") (pintype "bidirectional"))
      (node (ref "IC4") (pin "47") (pinfunction "VSS_3_47") (pintype "power_in"))
      (node (ref "IC4") (pin "8") (pinfunction "VSSA_8") (pintype "power_in"))
      (node (ref "IC5") (pin "1") (pinfunction "GND_1") (pintype "passive"))
      (node (ref "IC5") (pin "7") (pinfunction "GND_7") (pintype "passive"))
      (node (ref "IC6") (pin "5") (pinfunction "GND_5") (pintype "passive"))
      (node (ref "IC7") (pin "18") (pinfunction "GND_18") (pintype "passive"))
      (node (ref "IC7") (pin "19") (pinfunction "GND_19") (pintype "passive"))
      (node (ref "IC7") (pin "2") (pinfunction "GND_2") (pintype "passive"))
      (node (ref "IC8") (pin "4") (pinfunction "GND_4") (pintype "passive"))
      (node (ref "IC9") (pin "1") (pinfunction "TEMP_1") (pintype "passive"))
      (node (ref "IC9") (pin "3") (pinfunction "GND_3") (pintype "passive"))
      (node (ref "JP2") (pin "1") (pinfunction "1_1") (pintype "passive"))
      (node (ref "JP3") (pin "1") (pinfunction "VSS_1") (pintype "passive"))
      (node (ref "JP3") (pin "14") (pinfunction "WR_14") (pintype "passive"))
      (node (ref "JP3") (pin "15") (pinfunction "RD_15") (pintype "passive"))
      (node (ref "JP3") (pin "19") (pinfunction "D3_19") (pintype "passive"))
      (node (ref "JP3") (pin "20") (pinfunction "D4_20") (pintype "passive"))
      (node (ref "JP3") (pin "21") (pinfunction "D5_21") (pintype "passive"))
      (node (ref "JP3") (pin "22") (pinfunction "D6_22") (pintype "passive"))
      (node (ref "JP3") (pin "23") (pinfunction "D7_23") (pintype "passive"))
      (node (ref "JP3") (pin "25") (pinfunction "VSS_25") (pintype "passive"))
      (node (ref "JP3") (pin "7") (pinfunction "BS1_7") (pintype "passive"))
      (node (ref "JP3") (pin "8") (pinfunction "BS2_8") (pintype "passive"))
      (node (ref "JP3") (pin "9") (pinfunction "VSS_9") (pintype "passive"))
      (node (ref "JP4") (pin "1") (pinfunction "1_1") (pintype "passive"))
      (node (ref "K1") (pin "a") (pinfunction "a_a") (pintype "passive"))
      (node (ref "Q3") (pin "2") (pinfunction "E_2") (pintype "passive"))
      (node (ref "Q4") (pin "2") (pinfunction "E_2") (pintype "passive"))
      (node (ref "R12") (pin "1") (pinfunction "1_1") (pintype "passive"))
      (node (ref "R20") (pin "1") (pinfunction "1_1") (pintype "passive"))
      (node (ref "R22") (pin "1") (pinfunction "1_1") (pintype "passive"))
      (node (ref "R23") (pin "1") (pinfunction "1_1") (pintype "passive"))
      (node (ref "R27") (pin "1") (pinfunction "1_1") (pintype "passive"))
      (node (ref "R29") (pin "2") (pinfunction "2_2") (pintype "passive"))
      (node (ref "R3") (pin "2") (pinfunction "2_2") (pintype "passive"))
      (node (ref "R31") (pin "1") (pinfunction "1_1") (pintype "passive"))
      (node (ref "R5") (pin "2") (pinfunction "2_2") (pintype "passive"))
      (node (ref "SW_PWR1") (pin "2") (pinfunction "2_2") (pintype "passive"))
      (node (ref "SW_RST1") (pin "2") (pinfunction "2_2") (pintype "passive"))
      (node (ref "SW_RST2") (pin "2") (pinfunction "2_2") (pintype "passive"))
      (node (ref "USB1") (pin "A12") (pinfunction "GND_A12") (pintype "passive"))
      (node (ref "USB1") (pin "B12") (pinfunction "GND_B12") (pintype "passive"))
      (node (ref "X1") (pin "2") (pinfunction "2_2") (pintype "passive"))
      (node (ref "X1") (pin "4") (pinfunction "4_4") (pintype "passive"))
    )
    (net (code "42") (name "Net-(BUZZER1--)") (class "Default")
      (node (ref "BUZZER1") (pin "2") (pinfunction "-_2") (pintype "passive"))
      (node (ref "Q3") (pin "3") (pinfunction "C_3") (pintype "passive"))
    )
    (net (code "43") (name "Net-(C30-Pad2)") (class "Default")
      (node (ref "C30") (pin "2") (pinfunction "2_2") (pintype "passive"))
      (node (ref "DZx1") (pin "3") (pinfunction "3_3") (pintype "passive"))
      (node (ref "SW_PWR1") (pin "1") (pinfunction "1_1") (pintype "passive"))
    )
    (net (code "44") (name "Net-(D1-A)") (class "Default")
      (node (ref "D1") (pin "1") (pinfunction "A_1") (pintype "passive"))
      (node (ref "IC10") (pin "1") (pinfunction "SW_1") (pintype "passive"))
      (node (ref "L1") (pin "2") (pinfunction "2_2") (pintype "passive"))
    )
    (net (code "45") (name "Net-(E3-A)") (class "Default")
      (node (ref "E3") (pin "1") (pinfunction "A_1") (pintype "passive"))
      (node (ref "JP3") (pin "3") (pinfunction "VCOMH_3") (pintype "passive"))
    )
    (net (code "46") (name "Net-(IC2-AD0)") (class "Default")
      (node (ref "IC2") (pin "9") (pinfunction "AD0_9") (pintype "passive"))
      (node (ref "R3") (pin "1") (pinfunction "1_1") (pintype "passive"))
    )
    (net (code "47") (name "Net-(IC2-CPOUT)") (class "Default")
      (node (ref "C3") (pin "2") (pinfunction "2_2") (pintype "passive"))
      (node (ref "IC2") (pin "20") (pinfunction "CPOUT_20") (pintype "passive"))
    )
    (net (code "48") (name "Net-(IC2-REGOUT)") (class "Default")
      (node (ref "C4") (pin "1") (pinfunction "1_1") (pintype "passive"))
      (node (ref "IC2") (pin "10") (pinfunction "REGOUT_10") (pintype "passive"))
    )
    (net (code "49") (name "Net-(IC2-VLOGIC)") (class "Default")
      (node (ref "C1") (pin "1") (pinfunction "1_1") (pintype "passive"))
      (node (ref "IC2") (pin "8") (pinfunction "VLOGIC_8") (pintype "passive"))
    )
    (net (code "50") (name "Net-(IC3-VDD)") (class "Default")
      (node (ref "C2") (pin "2") (pinfunction "2_2") (pintype "passive"))
      (node (ref "IC3") (pin "8") (pinfunction "VDD_8") (pintype "passive"))
      (node (ref "R2") (pin "1") (pinfunction "1_1") (pintype "passive"))
    )
    (net (code "51") (name "Net-(IC5-CSB)") (class "Default")
      (node (ref "IC5") (pin "2") (pinfunction "CSB_2") (pintype "passive"))
      (node (ref "R10") (pin "1") (pinfunction "1_1") (pintype "passive"))
    )
    (net (code "52") (name "Net-(IC5-SDO)") (class "Default")
      (node (ref "IC5") (pin "5") (pinfunction "SDO_5") (pintype "passive"))
      (node (ref "R12") (pin "2") (pinfunction "2_2") (pintype "passive"))
    )
    (net (code "53") (name "Net-(IC6-32KHz)") (class "Default")
      (node (ref "IC6") (pin "1") (pinfunction "32KHz_1") (pintype "passive"))
      (node (ref "R7") (pin "2") (pinfunction "2_2") (pintype "passive"))
    )
    (net (code "54") (name "Net-(IC9-CE)") (class "Default")
      (node (ref "IC9") (pin "8") (pinfunction "CE_8") (pintype "passive"))
      (node (ref "R14") (pin "1") (pinfunction "1_1") (pintype "passive"))
    )
    (net (code "55") (name "Net-(IC9-PROG)") (class "Default")
      (node (ref "IC9") (pin "2") (pinfunction "PROG_2") (pintype "passive"))
      (node (ref "R23") (pin "2") (pinfunction "2_2") (pintype "passive"))
    )
    (net (code "56") (name "Net-(IC9-VCC)") (class "Default")
      (node (ref "C20") (pin "2") (pinfunction "2_2") (pintype "passive"))
      (node (ref "IC9") (pin "4") (pinfunction "VCC_4") (pintype "passive"))
      (node (ref "R15") (pin "1") (pinfunction "1_1") (pintype "passive"))
    )
    (net (code "57") (name "Net-(IC10-FB)") (class "Default")
      (node (ref "C21") (pin "1") (pinfunction "1_1") (pintype "passive"))
      (node (ref "IC10") (pin "3") (pinfunction "FB_3") (pintype "passive"))
      (node (ref "R18") (pin "1") (pinfunction "1_1") (pintype "passive"))
      (node (ref "R22") (pin "2") (pinfunction "2_2") (pintype "passive"))
    )
    (net (code "58") (name "Net-(IC11-C+)") (class "Default")
      (node (ref "C36") (pin "1") (pinfunction "1_1") (pintype "passive"))
      (node (ref "IC11") (pin "6") (pinfunction "C+_6") (pintype "passive"))
    )
    (net (code "59") (name "Net-(IC11-C-)") (class "Default")
      (node (ref "C36") (pin "2") (pinfunction "2_2") (pintype "passive"))
      (node (ref "IC11") (pin "4") (pinfunction "C-_4") (pintype "passive"))
    )
    (net (code "60") (name "Net-(JP3-IREF)") (class "Default")
      (node (ref "JP3") (pin "10") (pinfunction "IREF_10") (pintype "passive"))
      (node (ref "R20") (pin "2") (pinfunction "2_2") (pintype "passive"))
    )
    (net (code "61") (name "Net-(JP3-VDD)") (class "Default")
      (node (ref "C19") (pin "2") (pinfunction "2_2") (pintype "passive"))
      (node (ref "JP3") (pin "6") (pinfunction "VDD_6") (pintype "passive"))
    )
    (net (code "62") (name "Net-(LED1-A)") (class "Default")
      (node (ref "LED1") (pin "1") (pinfunction "A_1") (pintype "passive"))
      (node (ref "R13") (pin "1") (pinfunction "1_1") (pintype "passive"))
    )
    (net (code "63") (name "Net-(Q1-G)") (class "Default")
      (node (ref "DZx1") (pin "1") (pinfunction "1_1") (pintype "passive"))
      (node (ref "Q1") (pin "1") (pinfunction "G_1") (pintype "passive"))
      (node (ref "Q4") (pin "3") (pinfunction "C_3") (pintype "passive"))
      (node (ref "R28") (pin "2") (pinfunction "2_2") (pintype "passive"))
    )
    (net (code "64") (name "Net-(Q3-B)") (class "Default")
      (node (ref "Q3") (pin "1") (pinfunction "B_1") (pintype "passive"))
      (node (ref "R26") (pin "2") (pinfunction "2_2") (pintype "passive"))
      (node (ref "R27") (pin "2") (pinfunction "2_2") (pintype "passive"))
    )
    (net (code "65") (name "Net-(Q4-B)") (class "Default")
      (node (ref "Q4") (pin "1") (pinfunction "B_1") (pintype "passive"))
      (node (ref "R30") (pin "1") (pinfunction "1_1") (pintype "passive"))
      (node (ref "R31") (pin "2") (pinfunction "2_2") (pintype "passive"))
    )
    (net (code "66") (name "VBUS") (class "Default")
      (node (ref "D2") (pin "1") (pinfunction "A_1") (pintype "passive"))
      (node (ref "Q2") (pin "1") (pinfunction "G_1") (pintype "passive"))
      (node (ref "R14") (pin "2") (pinfunction "2_2") (pintype "passive"))
      (node (ref "R15") (pin "2") (pinfunction "2_2") (pintype "passive"))
      (node (ref "R29") (pin "1") (pinfunction "1_1") (pintype "passive"))
      (node (ref "USB1") (pin "A9") (pinfunction "VBUS_A9") (pintype "passive"))
      (node (ref "USB1") (pin "B9") (pinfunction "VBUS_B9") (pintype "passive"))
    )
    (net (code "67") (name "VLOUD") (class "Default")
      (node (ref "C22") (pin "2") (pinfunction "2_2") (pintype "passive"))
      (node (ref "C31") (pin "1") (pinfunction "1_1") (pintype "passive"))
      (node (ref "C33") (pin "1") (pinfunction "1_1") (pintype "passive"))
      (node (ref "C37") (pin "2") (pinfunction "2_2") (pintype "passive"))
      (node (ref "IC10") (pin "5") (pinfunction "VIN_5") (pintype "passive"))
      (node (ref "IC11") (pin "3") (pinfunction "EN_3") (pintype "passive"))
      (node (ref "IC11") (pin "5") (pinfunction "VIN_5") (pintype "passive"))
      (node (ref "IC12") (pin "1") (pinfunction "VIN_1") (pintype "passive"))
      (node (ref "IC12") (pin "3") (pinfunction "EN_3") (pintype "passive"))
      (node (ref "IC13") (pin "3") (pinfunction "VIN_3") (pintype "passive"))
      (node (ref "L1") (pin "1") (pinfunction "1_1") (pintype "passive"))
      (node (ref "Q1") (pin "3") (pinfunction "D_3") (pintype "passive"))
      (node (ref "R21") (pin "2") (pinfunction "2_2") (pintype "passive"))
      (node (ref "R25") (pin "1") (pinfunction "1_1") (pintype "passive"))
    )
    (net (code "68") (name "VOUT") (class "Default")
      (node (ref "D2") (pin "2") (pinfunction "K_2") (pintype "passive"))
      (node (ref "E4") (pin "1") (pinfunction "A_1") (pintype "passive"))
      (node (ref "IC6") (pin "6") (pinfunction "VBAT_6") (pintype "passive"))
      (node (ref "Q1") (pin "2") (pinfunction "S_2") (pintype "passive"))
      (node (ref "Q2") (pin "2") (pinfunction "S_2") (pintype "passive"))
      (node (ref "R28") (pin "1") (pinfunction "1_1") (pintype "passive"))
    )
    (net (code "69") (name "unconnected-(IC1-NC1-Pad8)") (class "Default")
      (node (ref "IC1") (pin "8") (pinfunction "NC1_8") (pintype "passive"))
    )
    (net (code "70") (name "unconnected-(IC1-NC2-Pad12)") (class "Default")
      (node (ref "IC1") (pin "12") (pinfunction "NC2_12") (pintype "passive"))
    )
    (net (code "71") (name "unconnected-(IC1-RSV-Pad3)") (class "Default")
      (node (ref "IC1") (pin "3") (pinfunction "RSV_3") (pintype "passive"))
    )
    (net (code "72") (name "unconnected-(IC1-SO-Pad6)") (class "Default")
      (node (ref "IC1") (pin "6") (pinfunction "SO_6") (pintype "passive"))
    )
    (net (code "73") (name "unconnected-(IC1-TST1-Pad1)") (class "Default")
      (node (ref "IC1") (pin "1") (pinfunction "TST1_1") (pintype "passive"))
    )
    (net (code "74") (name "unconnected-(IC1-TST2-Pad14)") (class "Default")
      (node (ref "IC1") (pin "14") (pinfunction "TST2_14") (pintype "passive"))
    )
    (net (code "75") (name "unconnected-(IC1-TST6-Pad9)") (class "Default")
      (node (ref "IC1") (pin "9") (pinfunction "TST6_9") (pintype "passive"))
    )
    (net (code "76") (name "unconnected-(IC2-AUX_CL-Pad7)") (class "Default")
      (node (ref "IC2") (pin "7") (pinfunction "AUX_CL_7") (pintype "passive"))
    )
    (net (code "77") (name "unconnected-(IC2-AUX_DA-Pad6)") (class "Default")
      (node (ref "IC2") (pin "6") (pinfunction "AUX_DA_6") (pintype "passive"))
    )
    (net (code "78") (name "unconnected-(IC2-CLKIN-Pad1)") (class "Default")
      (node (ref "IC2") (pin "1") (pinfunction "CLKIN_1") (pintype "passive"))
    )
    (net (code "79") (name "unconnected-(IC2-CLKOUT-Pad22)") (class "Default")
      (node (ref "IC2") (pin "22") (pinfunction "CLKOUT_22") (pintype "passive"))
    )
    (net (code "80") (name "unconnected-(IC2-FSYNC-Pad11)") (class "Default")
      (node (ref "IC2") (pin "11") (pinfunction "FSYNC_11") (pintype "passive"))
    )
    (net (code "81") (name "unconnected-(IC2-RESV-Pad19)") (class "Default")
      (node (ref "IC2") (pin "19") (pinfunction "RESV_19") (pintype "passive"))
    )
    (net (code "82") (name "unconnected-(IC2-RESV-Pad21)") (class "Default")
      (node (ref "IC2") (pin "21") (pinfunction "RESV_21") (pintype "passive"))
    )
    (net (code "83") (name "unconnected-(IC3-PIO-Pad2)") (class "Default")
      (node (ref "IC3") (pin "2") (pinfunction "PIO_2") (pintype "passive"))
    )
    (net (code "84") (name "unconnected-(IC3-SNS-Pad3)") (class "Default")
      (node (ref "IC3") (pin "3") (pinfunction "SNS_3") (pintype "passive"))
    )
    (net (code "85") (name "unconnected-(IC4-PA8{slash}TIM1_CH1-Pad29)") (class "Default")
      (node (ref "IC4") (pin "29") (pinfunction "PA8/TIM1_CH1_29") (pintype "bidirectional"))
    )
    (net (code "86") (name "unconnected-(IC4-PC14-OSC32_IN-Pad3)") (class "Default")
      (node (ref "IC4") (pin "3") (pinfunction "PC14-OSC32_IN_3") (pintype "bidirectional"))
    )
    (net (code "87") (name "unconnected-(IC4-PC15-OSC32_OUT-Pad4)") (class "Default")
      (node (ref "IC4") (pin "4") (pinfunction "PC15-OSC32_OUT_4") (pintype "bidirectional"))
    )
    (net (code "88") (name "unconnected-(IC4-TIM3_CH3{slash}PB0-Pad18)") (class "Default")
      (node (ref "IC4") (pin "18") (pinfunction "TIM3_CH3/PB0_18") (pintype "bidirectional"))
    )
    (net (code "89") (name "unconnected-(IC4-TIM4_CH3{slash}PB8-Pad45)") (class "Default")
      (node (ref "IC4") (pin "45") (pinfunction "TIM4_CH3/PB8_45") (pintype "bidirectional"))
    )
    (net (code "90") (name "unconnected-(IC6-RST#-Pad4)") (class "Default")
      (node (ref "IC6") (pin "4") (pinfunction "RST#_4") (pintype "passive"))
    )
    (net (code "91") (name "unconnected-(IC7-ADC-Pad3)") (class "Default")
      (node (ref "IC7") (pin "3") (pinfunction "ADC_3") (pintype "passive"))
    )
    (net (code "92") (name "unconnected-(IC7-ANT-Pad1)") (class "Default")
      (node (ref "IC7") (pin "1") (pinfunction "ANT_1") (pintype "passive"))
    )
    (net (code "93") (name "unconnected-(IC7-EN-Pad4)") (class "Default")
      (node (ref "IC7") (pin "4") (pinfunction "EN_4") (pintype "passive"))
    )
    (net (code "94") (name "unconnected-(IC7-IO2-Pad10)") (class "Default")
      (node (ref "IC7") (pin "10") (pinfunction "IO2_10") (pintype "passive"))
    )
    (net (code "95") (name "unconnected-(IC7-IO4-Pad12)") (class "Default")
      (node (ref "IC7") (pin "12") (pinfunction "IO4_12") (pintype "passive"))
    )
    (net (code "96") (name "unconnected-(IC7-IO5-Pad13)") (class "Default")
      (node (ref "IC7") (pin "13") (pinfunction "IO5_13") (pintype "passive"))
    )
    (net (code "97") (name "unconnected-(IC7-IO12-Pad7)") (class "Default")
      (node (ref "IC7") (pin "7") (pinfunction "IO12_7") (pintype "passive"))
    )
    (net (code "98") (name "unconnected-(IC7-IO13-Pad8)") (class "Default")
      (node (ref "IC7") (pin "8") (pinfunction "IO13_8") (pintype "passive"))
    )
    (net (code "99") (name "unconnected-(IC7-IO14-Pad6)") (class "Default")
      (node (ref "IC7") (pin "6") (pinfunction "IO14_6") (pintype "passive"))
    )
    (net (code "100") (name "unconnected-(IC7-IO15-Pad9)") (class "Default")
      (node (ref "IC7") (pin "9") (pinfunction "IO15_9") (pintype "passive"))
    )
    (net (code "101") (name "unconnected-(IC7-IO16-Pad5)") (class "Default")
      (node (ref "IC7") (pin "5") (pinfunction "IO16_5") (pintype "passive"))
    )
    (net (code "102") (name "unconnected-(IC12-NC-Pad4)") (class "Default")
      (node (ref "IC12") (pin "4") (pinfunction "NC_4") (pintype "passive"))
    )
    (net (code "103") (name "unconnected-(JP3-D2-Pad18)") (class "Default")
      (node (ref "JP3") (pin "18") (pinfunction "D2_18") (pintype "passive"))
    )
    (net (code "104") (name "unconnected-(USB1-CC1-PadA5)") (class "Default")
      (node (ref "USB1") (pin "A5") (pinfunction "CC1_A5") (pintype "passive"))
    )
    (net (code "105") (name "unconnected-(USB1-CC2-PadB5)") (class "Default")
      (node (ref "USB1") (pin "B5") (pinfunction "CC2_B5") (pintype "passive"))
    )
  )
)
